# E-P-015-R1_1.net
KiCad netlist of a schematic drawn in EAGLE
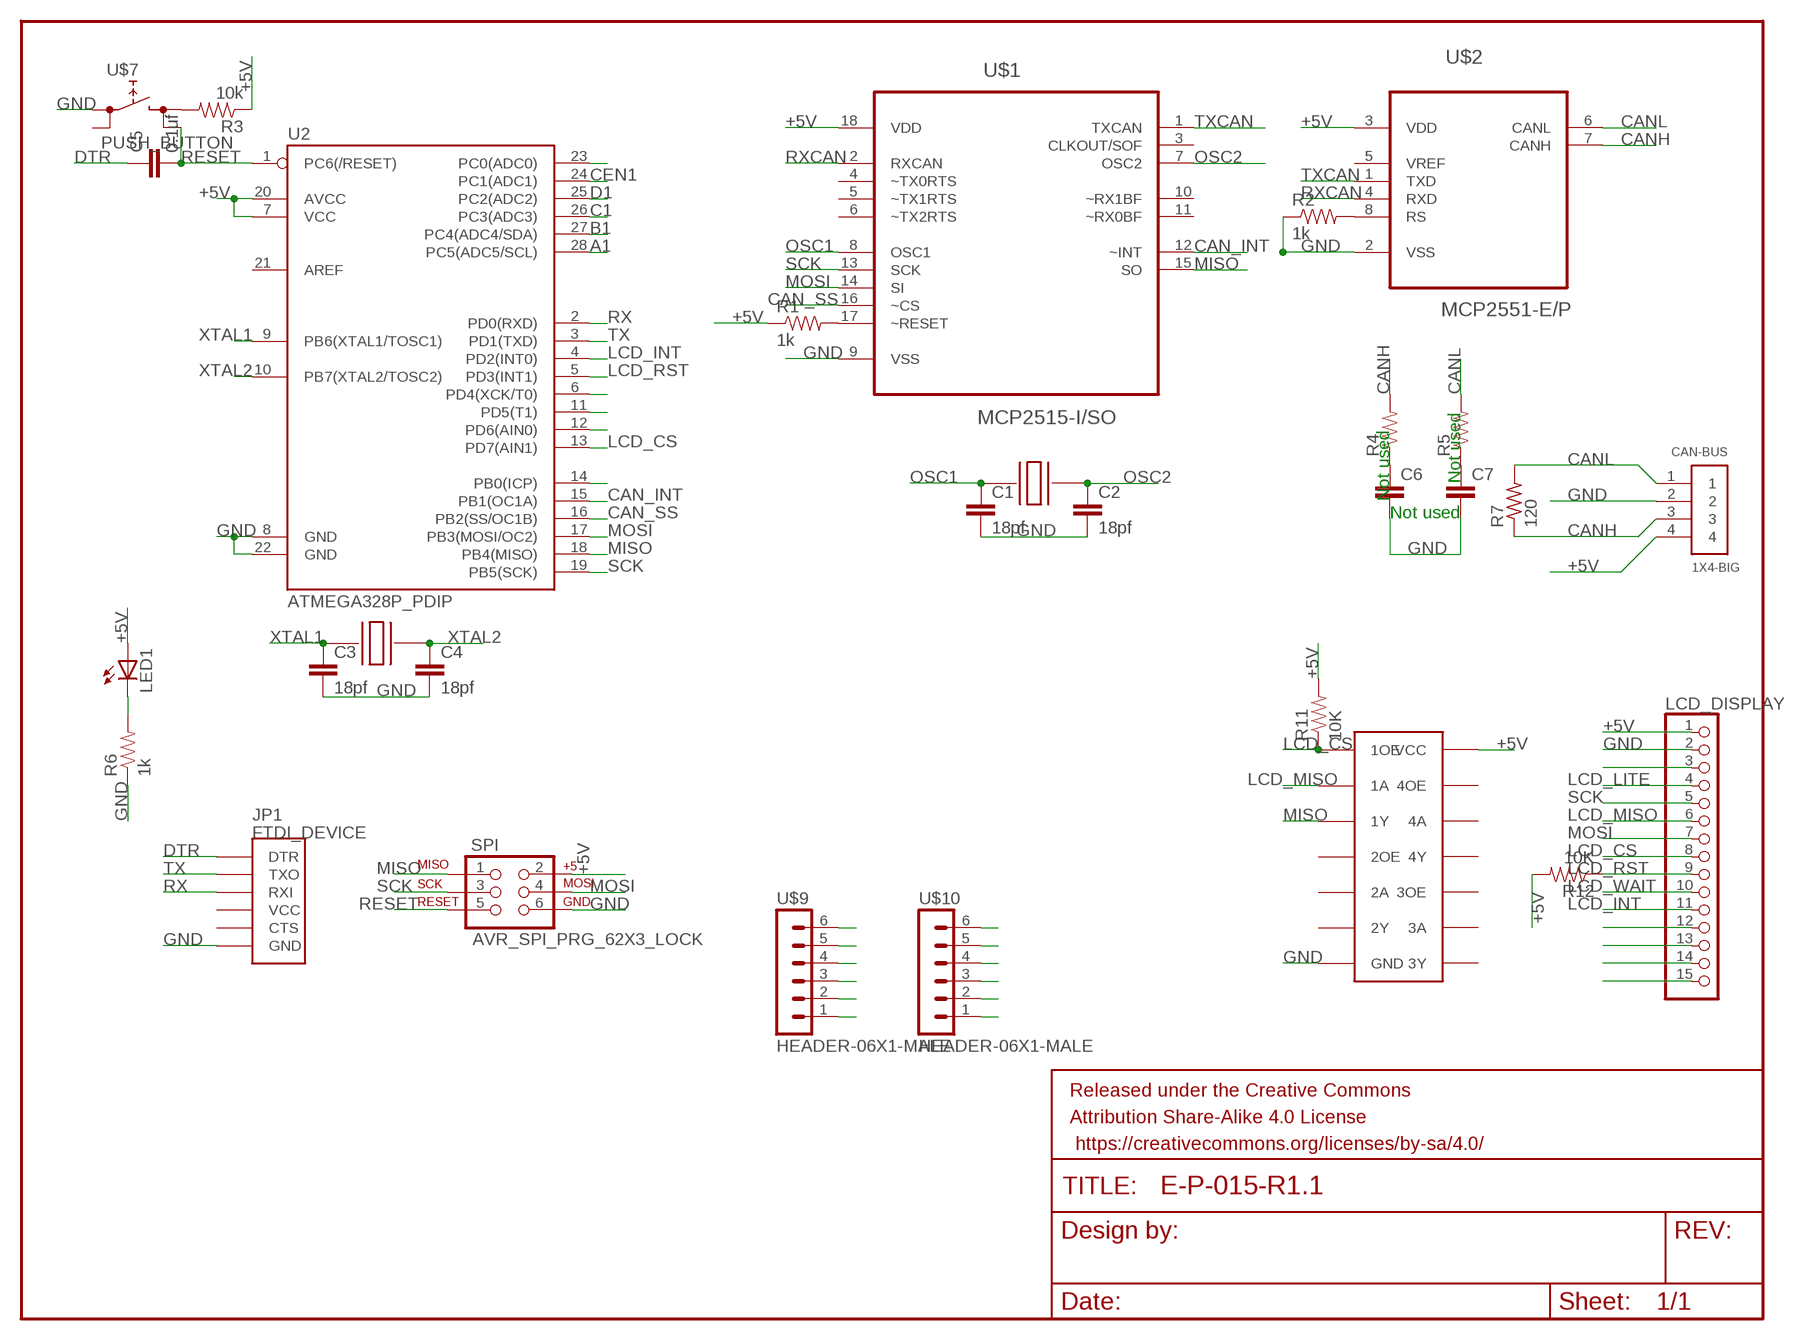
[diagram p0: schematic, sheet 1]

(export (version "E")
  (design (tool "Eeschema 10.0.6"))
  (components
    (comp (ref "C1")
      (value "18pf")
      (footprint "eagle-import:0805")
      (libsource (lib "eagle-import") (part "CAP0805"))
    )
    (comp (ref "C2")
      (value "18pf")
      (footprint "eagle-import:0805")
      (libsource (lib "eagle-import") (part "CAP0805"))
    )
    (comp (ref "C3")
      (value "18pf")
      (footprint "eagle-import:0805")
      (libsource (lib "eagle-import") (part "CAP0805"))
    )
    (comp (ref "C4")
      (value "18pf")
      (footprint "eagle-import:0805")
      (libsource (lib "eagle-import") (part "CAP0805"))
    )
    (comp (ref "C5")
      (value "0.1uf")
      (footprint "eagle-import:0805")
      (libsource (lib "eagle-import") (part "CAP0805"))
    )
    (comp (ref "C6")
      (value "CAP0805")
      (footprint "eagle-import:0805")
      (libsource (lib "eagle-import") (part "CAP0805"))
    )
    (comp (ref "C7")
      (value "CAP0805")
      (footprint "eagle-import:0805")
      (libsource (lib "eagle-import") (part "CAP0805"))
    )
    (comp (ref "CAN-BUS")
      (value "1X4-BIG")
      (footprint "eagle-import:1X04-BIG")
      (libsource (lib "eagle-import") (part "1X4-BIG"))
    )
    (comp (ref "FRAME1")
      (value "FRAME-LETTERNO_PACKAGE")
      (footprint "eagle-import:DUMMY")
      (fields (field (name "DESIGNER") "Nobody"))
      (libsource (lib "eagle-import") (part "FRAME-LETTERNO_PACKAGE"))
    )
    (comp (ref "JP1")
      (value "FTDI_DEVICE")
      (footprint "eagle-import:FTDI_DEVICE_SIDE")
      (libsource (lib "eagle-import") (part "FTDI_DEVICE"))
    )
    (comp (ref "LCD_DISPLAY")
      (value "PINHD-1X15")
      (footprint "eagle-import:1X15")
      (libsource (lib "eagle-import") (part "PINHD-1X15"))
    )
    (comp (ref "LED1")
      (value "LEDCHIPLED_1206")
      (footprint "eagle-import:CHIPLED_1206")
      (libsource (lib "eagle-import") (part "LEDCHIPLED_1206"))
    )
    (comp (ref "R1")
      (value "1k")
      (footprint "eagle-import:0805")
      (libsource (lib "eagle-import") (part "RESISTOR0805-RES"))
    )
    (comp (ref "R2")
      (value "1k")
      (footprint "eagle-import:0805")
      (libsource (lib "eagle-import") (part "RESISTOR0805-RES"))
    )
    (comp (ref "R3")
      (value "10k")
      (footprint "eagle-import:0805")
      (libsource (lib "eagle-import") (part "RESISTOR0805-RES"))
    )
    (comp (ref "R4")
      (value "RESISTOR0805-RES")
      (footprint "eagle-import:0805")
      (libsource (lib "eagle-import") (part "RESISTOR0805-RES"))
    )
    (comp (ref "R5")
      (value "RESISTOR0805-RES")
      (footprint "eagle-import:0805")
      (libsource (lib "eagle-import") (part "RESISTOR0805-RES"))
    )
    (comp (ref "R6")
      (value "1k")
      (footprint "eagle-import:0805")
      (libsource (lib "eagle-import") (part "RESISTOR0805-RES"))
    )
    (comp (ref "R7")
      (value "120")
      (footprint "eagle-import:M1206")
      (libsource (lib "eagle-import") (part "R-US_M1206"))
    )
    (comp (ref "R11")
      (value "10K")
      (footprint "eagle-import:0805")
      (libsource (lib "eagle-import") (part "SparkFun-Resistors_RESISTOR0805-RES"))
    )
    (comp (ref "R12")
      (value "10K")
      (footprint "eagle-import:0805")
      (libsource (lib "eagle-import") (part "SparkFun-Resistors_RESISTOR0805-RES"))
    )
    (comp (ref "SPI")
      (value "AVR_SPI_PRG_62X3_LOCK")
      (footprint "eagle-import:2X3_LOCK")
      (libsource (lib "eagle-import") (part "AVR_SPI_PRG_62X3_LOCK"))
    )
    (comp (ref "U$1")
      (value "MCP2515-I/SO")
      (footprint "eagle-import:SOIC127P1034X264-18N")
      (libsource (lib "eagle-import") (part "MCP2515-I/SO"))
    )
    (comp (ref "U$2")
      (value "MCP2551-E/P")
      (footprint "eagle-import:DIP254P762X432-8")
      (libsource (lib "eagle-import") (part "MCP2551-E/P"))
    )
    (comp (ref "U$3")
      (value "CRYSTAL")
      (footprint "eagle-import:7A_CRYSTAL")
      (libsource (lib "eagle-import") (part "CRYSTAL"))
    )
    (comp (ref "U$4")
      (value "CRYSTAL")
      (footprint "eagle-import:7A_CRYSTAL")
      (libsource (lib "eagle-import") (part "CRYSTAL"))
    )
    (comp (ref "U$5")
      (value "SN74HC125N")
      (footprint "eagle-import:296-1572-5-ND")
      (libsource (lib "eagle-import") (part "SN74HC125N"))
    )
    (comp (ref "U$7")
      (value "PUSH_BUTTON")
      (footprint "eagle-import:PUSHBUTTON")
      (libsource (lib "eagle-import") (part "PUSH_BUTTON"))
    )
    (comp (ref "U$9")
      (value "HEADER-06X1-MALE")
      (footprint "eagle-import:06X1-PTH")
      (libsource (lib "eagle-import") (part "HEADER-06X1?-MALE"))
    )
    (comp (ref "U$10")
      (value "HEADER-06X1-MALE")
      (footprint "eagle-import:06X1-PTH")
      (libsource (lib "eagle-import") (part "HEADER-06X1?-MALE"))
    )
    (comp (ref "U2")
      (value "ATMEGA328P_PDIP")
      (footprint "eagle-import:DIL28-3")
      (libsource (lib "eagle-import") (part "ATMEGA328P_PDIP"))
    )
  )
  (nets
    (net (code "1") (name "/+5V") (class "Default")
      (node (ref "CAN-BUS") (pin "4") (pinfunction "4_4") (pintype "bidirectional"))
      (node (ref "LCD_DISPLAY") (pin "1") (pinfunction "1_1") (pintype "passive"))
      (node (ref "LED1") (pin "A") (pinfunction "A_A") (pintype "passive"))
      (node (ref "R1") (pin "1") (pinfunction "1_1") (pintype "passive"))
      (node (ref "R11") (pin "2") (pinfunction "2_2") (pintype "passive"))
      (node (ref "R12") (pin "2") (pinfunction "2_2") (pintype "passive"))
      (node (ref "R3") (pin "1") (pinfunction "1_1") (pintype "passive"))
      (node (ref "SPI") (pin "2") (pinfunction "2_2") (pintype "passive"))
      (node (ref "U$1") (pin "18") (pinfunction "VDD_18") (pintype "power_in"))
      (node (ref "U$2") (pin "3") (pinfunction "VDD_3") (pintype "power_in"))
      (node (ref "U$5") (pin "P$14") (pinfunction "VCC_P$14") (pintype "bidirectional"))
      (node (ref "U2") (pin "20") (pinfunction "AVCC_20") (pintype "bidirectional"))
      (node (ref "U2") (pin "7") (pinfunction "VCC_7") (pintype "bidirectional"))
    )
    (net (code "2") (name "/A1") (class "Default")
      (node (ref "U$9") (pin "6") (pinfunction "6_6") (pintype "passive"))
      (node (ref "U2") (pin "28") (pinfunction "PC5(ADC5/SCL)_28") (pintype "bidirectional"))
    )
    (net (code "3") (name "/A2") (class "Default")
      (node (ref "U$10") (pin "6") (pinfunction "6_6") (pintype "passive"))
      (node (ref "U2") (pin "23") (pinfunction "PC0(ADC0)_23") (pintype "bidirectional"))
    )
    (net (code "4") (name "/B1") (class "Default")
      (node (ref "U$9") (pin "5") (pinfunction "5_5") (pintype "passive"))
      (node (ref "U2") (pin "27") (pinfunction "PC4(ADC4/SDA)_27") (pintype "bidirectional"))
    )
    (net (code "5") (name "/B2") (class "Default")
      (node (ref "U$10") (pin "5") (pinfunction "5_5") (pintype "passive"))
      (node (ref "U2") (pin "6") (pinfunction "PD4(XCK/T0)_6") (pintype "bidirectional"))
    )
    (net (code "6") (name "/C1") (class "Default")
      (node (ref "U$9") (pin "4") (pinfunction "4_4") (pintype "passive"))
      (node (ref "U2") (pin "26") (pinfunction "PC3(ADC3)_26") (pintype "bidirectional"))
    )
    (net (code "7") (name "/C2") (class "Default")
      (node (ref "U$10") (pin "4") (pinfunction "4_4") (pintype "passive"))
      (node (ref "U2") (pin "11") (pinfunction "PD5(T1)_11") (pintype "bidirectional"))
    )
    (net (code "8") (name "/CANH") (class "Default")
      (node (ref "CAN-BUS") (pin "3") (pinfunction "3_3") (pintype "bidirectional"))
      (node (ref "R4") (pin "2") (pinfunction "2_2") (pintype "passive"))
      (node (ref "R7") (pin "1") (pinfunction "1_1") (pintype "passive"))
      (node (ref "U$2") (pin "7") (pinfunction "CANH_7") (pintype "output"))
    )
    (net (code "9") (name "/CANL") (class "Default")
      (node (ref "CAN-BUS") (pin "1") (pinfunction "1_1") (pintype "bidirectional"))
      (node (ref "R5") (pin "2") (pinfunction "2_2") (pintype "passive"))
      (node (ref "R7") (pin "2") (pinfunction "2_2") (pintype "passive"))
      (node (ref "U$2") (pin "6") (pinfunction "CANL_6") (pintype "output"))
    )
    (net (code "10") (name "/CAN_INT") (class "Default")
      (node (ref "U$1") (pin "12") (pinfunction "~{INT}_12") (pintype "output"))
      (node (ref "U2") (pin "15") (pinfunction "PB1(OC1A)_15") (pintype "bidirectional"))
    )
    (net (code "11") (name "/CAN_SS") (class "Default")
      (node (ref "U$1") (pin "16") (pinfunction "~{CS}_16") (pintype "input"))
      (node (ref "U2") (pin "16") (pinfunction "PB2(SS/OC1B)_16") (pintype "bidirectional"))
    )
    (net (code "12") (name "/CEN1") (class "Default")
      (node (ref "U$9") (pin "2") (pinfunction "2_2") (pintype "passive"))
      (node (ref "U2") (pin "24") (pinfunction "PC1(ADC1)_24") (pintype "bidirectional"))
    )
    (net (code "13") (name "/CEN2") (class "Default")
      (node (ref "U$10") (pin "2") (pinfunction "2_2") (pintype "passive"))
      (node (ref "U2") (pin "14") (pinfunction "PB0(ICP)_14") (pintype "bidirectional"))
    )
    (net (code "14") (name "/D1") (class "Default")
      (node (ref "U$9") (pin "3") (pinfunction "3_3") (pintype "passive"))
      (node (ref "U2") (pin "25") (pinfunction "PC2(ADC2)_25") (pintype "bidirectional"))
    )
    (net (code "15") (name "/D2") (class "Default")
      (node (ref "U$10") (pin "3") (pinfunction "3_3") (pintype "passive"))
      (node (ref "U2") (pin "12") (pinfunction "PD6(AIN0)_12") (pintype "bidirectional"))
    )
    (net (code "16") (name "/DTR") (class "Default")
      (node (ref "C5") (pin "1") (pinfunction "1_1") (pintype "passive"))
      (node (ref "JP1") (pin "P$1") (pinfunction "DTR_P$1") (pintype "bidirectional"))
    )
    (net (code "17") (name "/GND") (class "Default")
      (node (ref "C1") (pin "2") (pinfunction "2_2") (pintype "passive"))
      (node (ref "C2") (pin "2") (pinfunction "2_2") (pintype "passive"))
      (node (ref "C3") (pin "2") (pinfunction "2_2") (pintype "passive"))
      (node (ref "C4") (pin "2") (pinfunction "2_2") (pintype "passive"))
      (node (ref "C6") (pin "2") (pinfunction "2_2") (pintype "passive"))
      (node (ref "C7") (pin "2") (pinfunction "2_2") (pintype "passive"))
      (node (ref "CAN-BUS") (pin "2") (pinfunction "2_2") (pintype "bidirectional"))
      (node (ref "JP1") (pin "P$6") (pinfunction "GND_P$6") (pintype "bidirectional"))
      (node (ref "LCD_DISPLAY") (pin "2") (pinfunction "2_2") (pintype "passive"))
      (node (ref "R2") (pin "1") (pinfunction "1_1") (pintype "passive"))
      (node (ref "R6") (pin "1") (pinfunction "1_1") (pintype "passive"))
      (node (ref "SPI") (pin "6") (pinfunction "6_6") (pintype "passive"))
      (node (ref "U$1") (pin "9") (pinfunction "VSS_9") (pintype "power_in"))
      (node (ref "U$10") (pin "1") (pinfunction "1_1") (pintype "passive"))
      (node (ref "U$2") (pin "2") (pinfunction "VSS_2") (pintype "passive"))
      (node (ref "U$5") (pin "P$7") (pinfunction "GND_P$7") (pintype "bidirectional"))
      (node (ref "U$7") (pin "L1") (pinfunction "L_L1") (pintype "passive"))
      (node (ref "U$9") (pin "1") (pinfunction "1_1") (pintype "passive"))
      (node (ref "U2") (pin "22") (pinfunction "GND_22") (pintype "bidirectional"))
      (node (ref "U2") (pin "8") (pinfunction "GND_8") (pintype "bidirectional"))
    )
    (net (code "18") (name "/LCD_CS") (class "Default")
      (node (ref "LCD_DISPLAY") (pin "8") (pinfunction "8_8") (pintype "passive"))
      (node (ref "R11") (pin "1") (pinfunction "1_1") (pintype "passive"))
      (node (ref "U$5") (pin "P$1") (pinfunction "1OE_P$1") (pintype "bidirectional"))
      (node (ref "U2") (pin "13") (pinfunction "PD7(AIN1)_13") (pintype "bidirectional"))
    )
    (net (code "19") (name "/LCD_INT") (class "Default")
      (node (ref "LCD_DISPLAY") (pin "11") (pinfunction "11_11") (pintype "passive"))
      (node (ref "U2") (pin "4") (pinfunction "PD2(INT0)_4") (pintype "bidirectional"))
    )
    (net (code "20") (name "/LCD_LITE") (class "Default")
      (node (ref "LCD_DISPLAY") (pin "4") (pinfunction "4_4") (pintype "passive"))
    )
    (net (code "21") (name "/LCD_MISO") (class "Default")
      (node (ref "LCD_DISPLAY") (pin "6") (pinfunction "6_6") (pintype "passive"))
      (node (ref "U$5") (pin "P$2") (pinfunction "1A_P$2") (pintype "bidirectional"))
    )
    (net (code "22") (name "/LCD_RST") (class "Default")
      (node (ref "LCD_DISPLAY") (pin "9") (pinfunction "9_9") (pintype "passive"))
      (node (ref "R12") (pin "1") (pinfunction "1_1") (pintype "passive"))
      (node (ref "U2") (pin "5") (pinfunction "PD3(INT1)_5") (pintype "bidirectional"))
    )
    (net (code "23") (name "/LCD_WAIT") (class "Default")
      (node (ref "LCD_DISPLAY") (pin "10") (pinfunction "10_10") (pintype "passive"))
    )
    (net (code "24") (name "/MISO") (class "Default")
      (node (ref "SPI") (pin "1") (pinfunction "1_1") (pintype "passive"))
      (node (ref "U$1") (pin "15") (pinfunction "SO_15") (pintype "output"))
      (node (ref "U$5") (pin "P$3") (pinfunction "1Y_P$3") (pintype "bidirectional"))
      (node (ref "U2") (pin "18") (pinfunction "PB4(MISO)_18") (pintype "bidirectional"))
    )
    (net (code "25") (name "/MOSI") (class "Default")
      (node (ref "LCD_DISPLAY") (pin "7") (pinfunction "7_7") (pintype "passive"))
      (node (ref "SPI") (pin "4") (pinfunction "4_4") (pintype "passive"))
      (node (ref "U$1") (pin "14") (pinfunction "SI_14") (pintype "input"))
      (node (ref "U2") (pin "17") (pinfunction "PB3(MOSI/OC2)_17") (pintype "bidirectional"))
    )
    (net (code "26") (name "/OSC1") (class "Default")
      (node (ref "C1") (pin "1") (pinfunction "1_1") (pintype "passive"))
      (node (ref "U$1") (pin "8") (pinfunction "OSC1_8") (pintype "input"))
      (node (ref "U$3") (pin "P$2") (pinfunction "P$2_P$2") (pintype "bidirectional"))
    )
    (net (code "27") (name "/OSC2") (class "Default")
      (node (ref "C2") (pin "1") (pinfunction "1_1") (pintype "passive"))
      (node (ref "U$1") (pin "7") (pinfunction "OSC2_7") (pintype "output"))
      (node (ref "U$3") (pin "P$1") (pinfunction "P$1_P$1") (pintype "bidirectional"))
    )
    (net (code "28") (name "/RESET") (class "Default")
      (node (ref "C5") (pin "2") (pinfunction "2_2") (pintype "passive"))
      (node (ref "SPI") (pin "5") (pinfunction "5_5") (pintype "passive"))
      (node (ref "U$7") (pin "R2") (pinfunction "R_R2") (pintype "passive"))
      (node (ref "U2") (pin "1") (pinfunction "PC6(/RESET)_1") (pintype "bidirectional"))
    )
    (net (code "29") (name "/RX") (class "Default")
      (node (ref "JP1") (pin "P$3") (pinfunction "RXI_P$3") (pintype "bidirectional"))
      (node (ref "U2") (pin "2") (pinfunction "PD0(RXD)_2") (pintype "bidirectional"))
    )
    (net (code "30") (name "/RXCAN") (class "Default")
      (node (ref "U$1") (pin "2") (pinfunction "RXCAN_2") (pintype "input"))
      (node (ref "U$2") (pin "4") (pinfunction "RXD_4") (pintype "input"))
    )
    (net (code "31") (name "/SCK") (class "Default")
      (node (ref "LCD_DISPLAY") (pin "5") (pinfunction "5_5") (pintype "passive"))
      (node (ref "SPI") (pin "3") (pinfunction "3_3") (pintype "passive"))
      (node (ref "U$1") (pin "13") (pinfunction "SCK_13") (pintype "input"))
      (node (ref "U2") (pin "19") (pinfunction "PB5(SCK)_19") (pintype "bidirectional"))
    )
    (net (code "32") (name "/TX") (class "Default")
      (node (ref "JP1") (pin "P$2") (pinfunction "TXO_P$2") (pintype "bidirectional"))
      (node (ref "U2") (pin "3") (pinfunction "PD1(TXD)_3") (pintype "bidirectional"))
    )
    (net (code "33") (name "/TXCAN") (class "Default")
      (node (ref "U$1") (pin "1") (pinfunction "TXCAN_1") (pintype "output"))
      (node (ref "U$2") (pin "1") (pinfunction "TXD_1") (pintype "input"))
    )
    (net (code "34") (name "/XTAL1") (class "Default")
      (node (ref "C3") (pin "1") (pinfunction "1_1") (pintype "passive"))
      (node (ref "U$4") (pin "P$2") (pinfunction "P$2_P$2") (pintype "bidirectional"))
      (node (ref "U2") (pin "9") (pinfunction "PB6(XTAL1/TOSC1)_9") (pintype "bidirectional"))
    )
    (net (code "35") (name "/XTAL2") (class "Default")
      (node (ref "C4") (pin "1") (pinfunction "1_1") (pintype "passive"))
      (node (ref "U$4") (pin "P$1") (pinfunction "P$1_P$1") (pintype "bidirectional"))
      (node (ref "U2") (pin "10") (pinfunction "PB7(XTAL2/TOSC2)_10") (pintype "bidirectional"))
    )
    (net (code "36") (name "Net-(C6-Pad1)") (class "Default")
      (node (ref "C6") (pin "1") (pinfunction "1_1") (pintype "passive"))
      (node (ref "R4") (pin "1") (pinfunction "1_1") (pintype "passive"))
    )
    (net (code "37") (name "Net-(C7-Pad1)") (class "Default")
      (node (ref "C7") (pin "1") (pinfunction "1_1") (pintype "passive"))
      (node (ref "R5") (pin "1") (pinfunction "1_1") (pintype "passive"))
    )
    (net (code "38") (name "Net-(LED1-PadC)") (class "Default")
      (node (ref "LED1") (pin "C") (pinfunction "C_C") (pintype "passive"))
      (node (ref "R6") (pin "2") (pinfunction "2_2") (pintype "passive"))
    )
    (net (code "39") (name "Net-(R3-Pad2)") (class "Default")
      (node (ref "R3") (pin "2") (pinfunction "2_2") (pintype "passive"))
      (node (ref "U$7") (pin "R1") (pinfunction "R_R1") (pintype "passive"))
    )
    (net (code "40") (name "Net-(U$1-~{RESET})") (class "Default")
      (node (ref "R1") (pin "2") (pinfunction "2_2") (pintype "passive"))
      (node (ref "U$1") (pin "17") (pinfunction "~{RESET}_17") (pintype "input"))
    )
    (net (code "41") (name "Net-(U$2-RS)") (class "Default")
      (node (ref "R2") (pin "2") (pinfunction "2_2") (pintype "passive"))
      (node (ref "U$2") (pin "8") (pinfunction "RS_8") (pintype "input"))
    )
    (net (code "42") (name "unconnected-(JP1-CTS-PadP$5)") (class "Default")
      (node (ref "JP1") (pin "P$5") (pinfunction "CTS_P$5") (pintype "bidirectional"))
    )
    (net (code "43") (name "unconnected-(JP1-VCC-PadP$4)") (class "Default")
      (node (ref "JP1") (pin "P$4") (pinfunction "VCC_P$4") (pintype "bidirectional"))
    )
    (net (code "44") (name "unconnected-(LCD_DISPLAY-Pad3)") (class "Default")
      (node (ref "LCD_DISPLAY") (pin "3") (pinfunction "3_3") (pintype "passive"))
    )
    (net (code "45") (name "unconnected-(LCD_DISPLAY-Pad12)") (class "Default")
      (node (ref "LCD_DISPLAY") (pin "12") (pinfunction "12_12") (pintype "passive"))
    )
    (net (code "46") (name "unconnected-(LCD_DISPLAY-Pad13)") (class "Default")
      (node (ref "LCD_DISPLAY") (pin "13") (pinfunction "13_13") (pintype "passive"))
    )
    (net (code "47") (name "unconnected-(LCD_DISPLAY-Pad14)") (class "Default")
      (node (ref "LCD_DISPLAY") (pin "14") (pinfunction "14_14") (pintype "passive"))
    )
    (net (code "48") (name "unconnected-(LCD_DISPLAY-Pad15)") (class "Default")
      (node (ref "LCD_DISPLAY") (pin "15") (pinfunction "15_15") (pintype "passive"))
    )
    (net (code "49") (name "unconnected-(U$1-CLKOUT{slash}SOF-Pad3)") (class "Default")
      (node (ref "U$1") (pin "3") (pinfunction "CLKOUT/SOF_3") (pintype "output"))
    )
    (net (code "50") (name "unconnected-(U$1-~{RX0BF}-Pad11)") (class "Default")
      (node (ref "U$1") (pin "11") (pinfunction "~{RX0BF}_11") (pintype "output"))
    )
    (net (code "51") (name "unconnected-(U$1-~{RX1BF}-Pad10)") (class "Default")
      (node (ref "U$1") (pin "10") (pinfunction "~{RX1BF}_10") (pintype "output"))
    )
    (net (code "52") (name "unconnected-(U$1-~{TX0RTS}-Pad4)") (class "Default")
      (node (ref "U$1") (pin "4") (pinfunction "~{TX0RTS}_4") (pintype "input"))
    )
    (net (code "53") (name "unconnected-(U$1-~{TX1RTS}-Pad5)") (class "Default")
      (node (ref "U$1") (pin "5") (pinfunction "~{TX1RTS}_5") (pintype "input"))
    )
    (net (code "54") (name "unconnected-(U$1-~{TX2RTS}-Pad6)") (class "Default")
      (node (ref "U$1") (pin "6") (pinfunction "~{TX2RTS}_6") (pintype "input"))
    )
    (net (code "55") (name "unconnected-(U$2-VREF-Pad5)") (class "Default")
      (node (ref "U$2") (pin "5") (pinfunction "VREF_5") (pintype "input"))
    )
    (net (code "56") (name "unconnected-(U$5-2A-PadP$5)") (class "Default")
      (node (ref "U$5") (pin "P$5") (pinfunction "2A_P$5") (pintype "bidirectional"))
    )
    (net (code "57") (name "unconnected-(U$5-2OE-PadP$4)") (class "Default")
      (node (ref "U$5") (pin "P$4") (pinfunction "2OE_P$4") (pintype "bidirectional"))
    )
    (net (code "58") (name "unconnected-(U$5-2Y-PadP$6)") (class "Default")
      (node (ref "U$5") (pin "P$6") (pinfunction "2Y_P$6") (pintype "bidirectional"))
    )
    (net (code "59") (name "unconnected-(U$5-3A-PadP$9)") (class "Default")
      (node (ref "U$5") (pin "P$9") (pinfunction "3A_P$9") (pintype "bidirectional"))
    )
    (net (code "60") (name "unconnected-(U$5-3OE-PadP$10)") (class "Default")
      (node (ref "U$5") (pin "P$10") (pinfunction "3OE_P$10") (pintype "bidirectional"))
    )
    (net (code "61") (name "unconnected-(U$5-3Y-PadP$8)") (class "Default")
      (node (ref "U$5") (pin "P$8") (pinfunction "3Y_P$8") (pintype "bidirectional"))
    )
    (net (code "62") (name "unconnected-(U$5-4A-PadP$12)") (class "Default")
      (node (ref "U$5") (pin "P$12") (pinfunction "4A_P$12") (pintype "bidirectional"))
    )
    (net (code "63") (name "unconnected-(U$5-4OE-PadP$13)") (class "Default")
      (node (ref "U$5") (pin "P$13") (pinfunction "4OE_P$13") (pintype "bidirectional"))
    )
    (net (code "64") (name "unconnected-(U$5-4Y-PadP$11)") (class "Default")
      (node (ref "U$5") (pin "P$11") (pinfunction "4Y_P$11") (pintype "bidirectional"))
    )
    (net (code "65") (name "unconnected-(U$7-L-PadL2)") (class "Default")
      (node (ref "U$7") (pin "L2") (pinfunction "L_L2") (pintype "passive"))
    )
    (net (code "66") (name "unconnected-(U2-AREF-Pad21)") (class "Default")
      (node (ref "U2") (pin "21") (pinfunction "AREF_21") (pintype "bidirectional"))
    )
  )
)
